# Stove_Light.net
KiCad netlist of a schematic drawn in Altium Designer
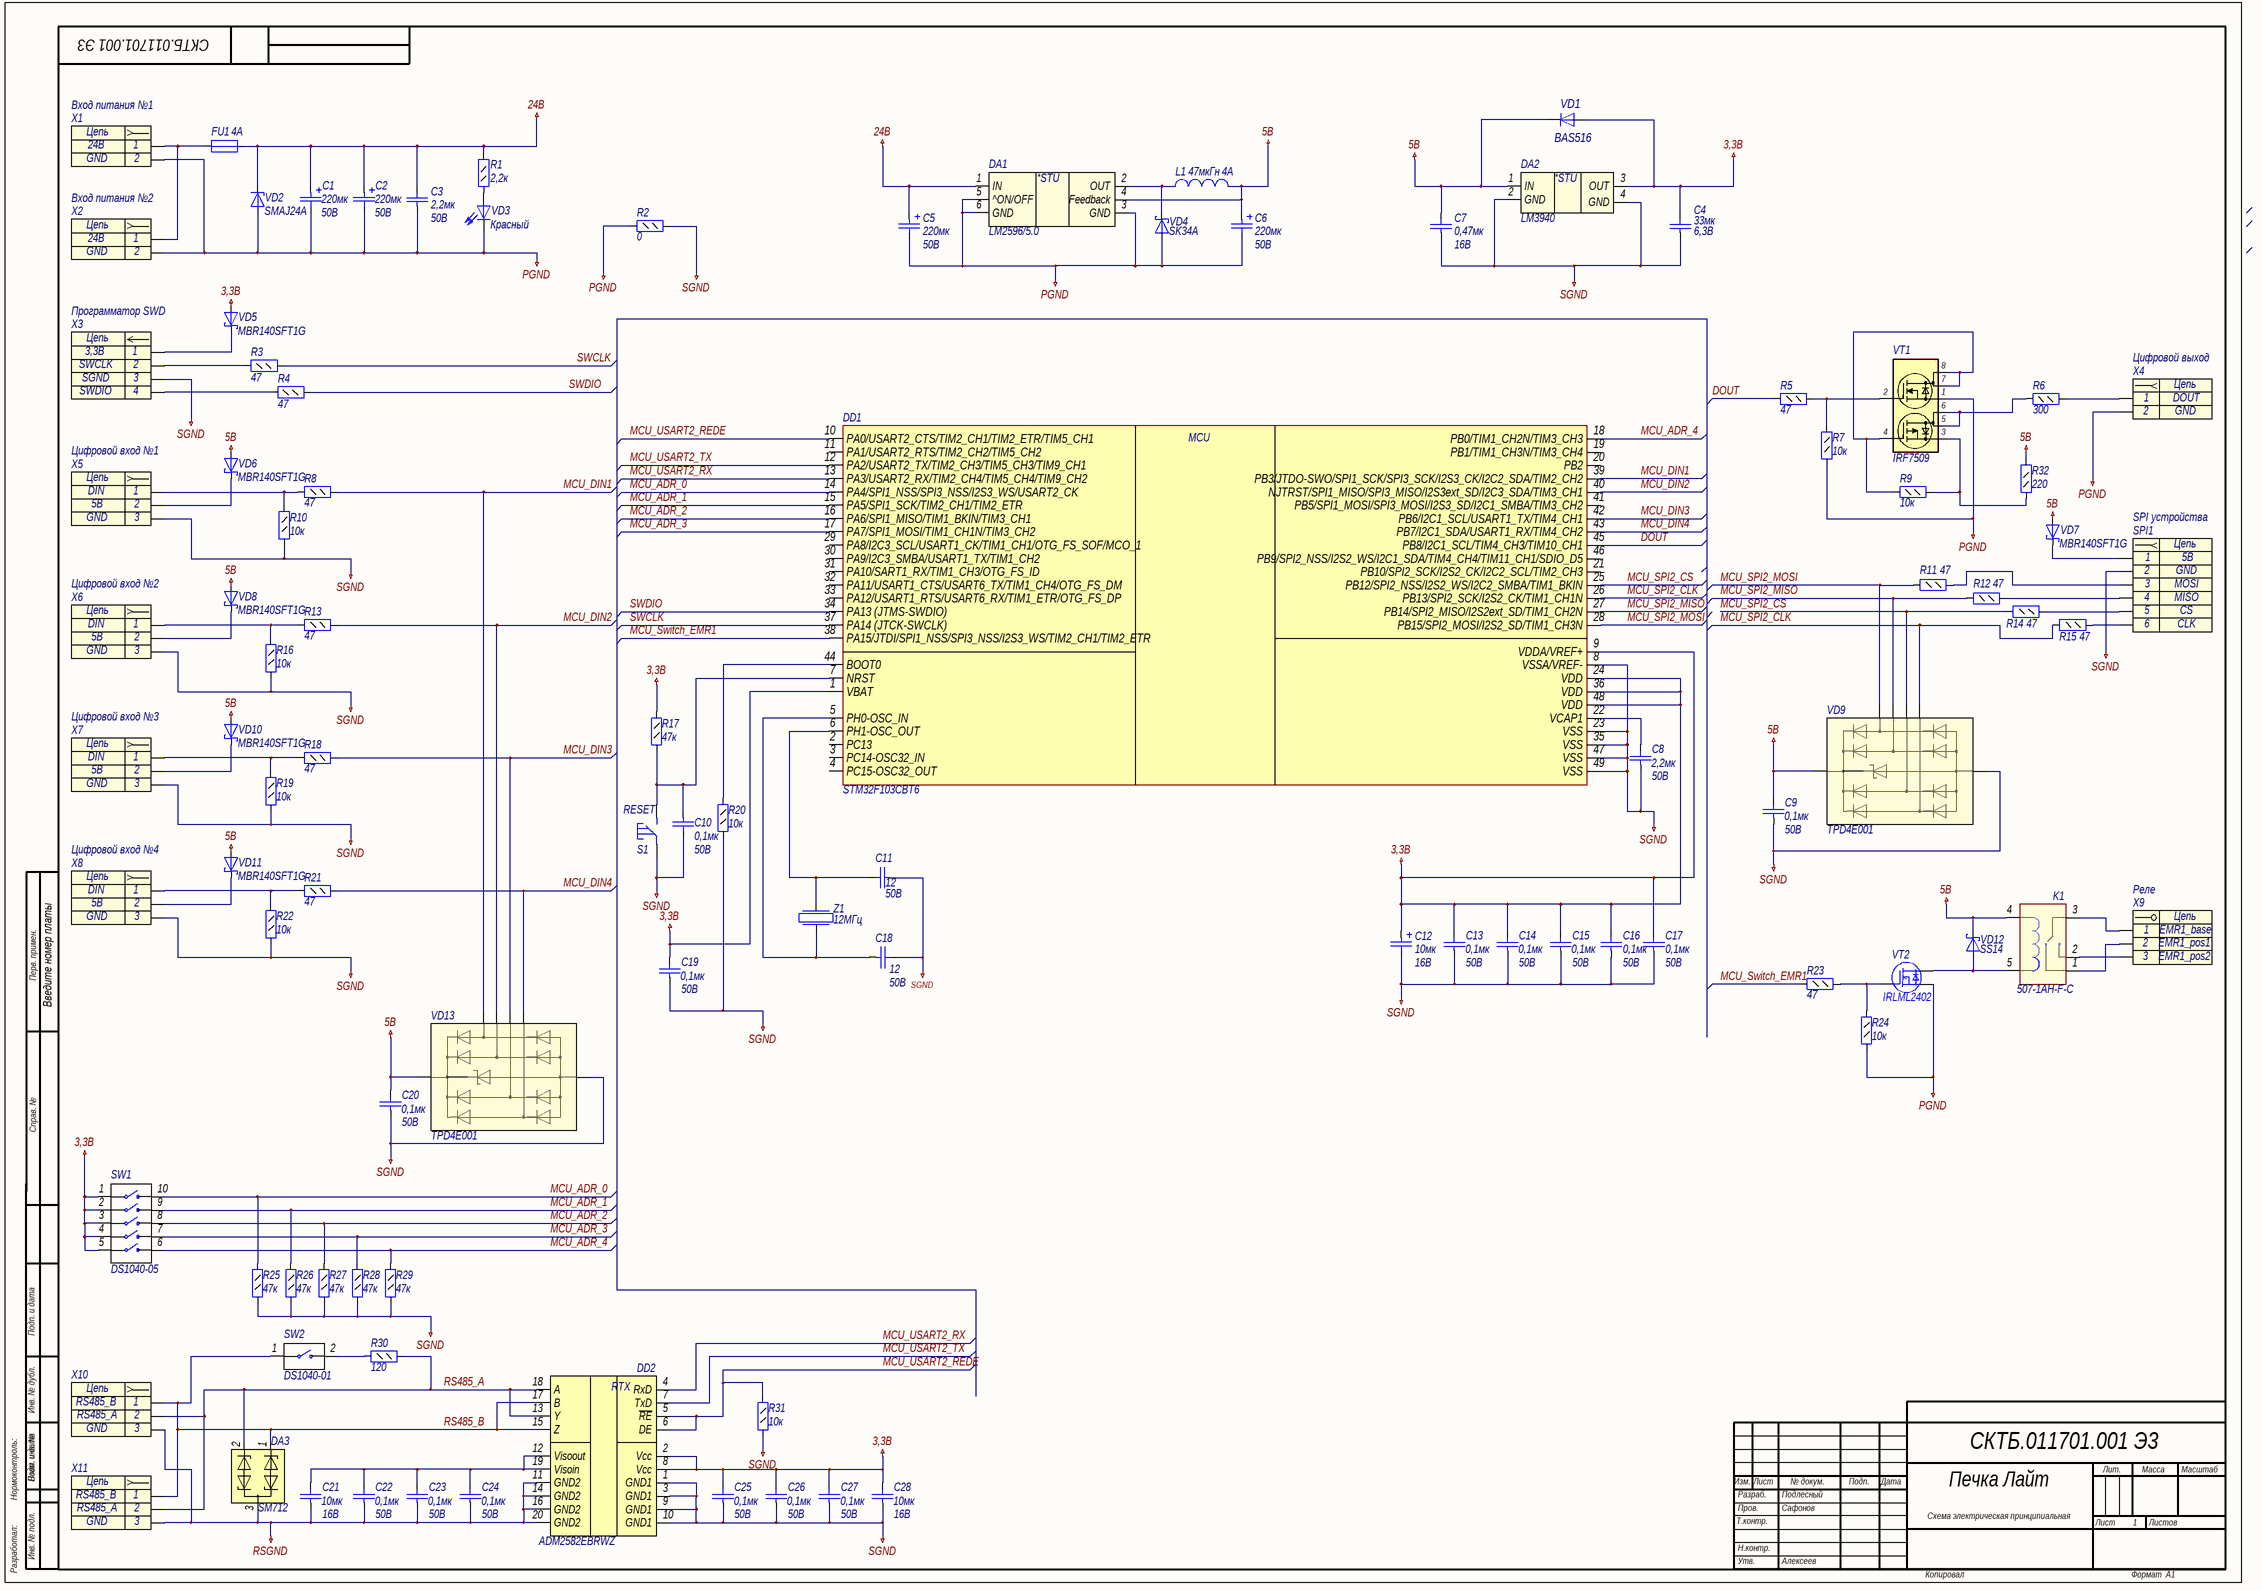
[diagram p0: Stove_Light.SchDoc]

(export (version "E")
  (design (tool "Eeschema 10.0.6"))
  (components
    (comp (ref "C1")
      (value "220мк")
      (footprint "Stove_Light:Cap_SMD_radial_polar(10x10.5)")
      (description "Конденсатор поляризованный")
      (fields (field (name "VOLTAGE") "50В"))
      (libsource (lib "Stove_Light") (part "Capacitor_pol"))
    )
    (comp (ref "C2")
      (value "220мк")
      (footprint "Stove_Light:Cap_SMD_radial_polar(10x10.5)")
      (description "Конденсатор поляризованный")
      (fields (field (name "VOLTAGE") "50В"))
      (libsource (lib "Stove_Light") (part "Capacitor_pol"))
    )
    (comp (ref "C3")
      (value "2,2мк")
      (footprint "Stove_Light:C1206")
      (description "Конденсатор")
      (fields (field (name "VOLTAGE") "50В"))
      (libsource (lib "Stove_Light") (part "Capacitor"))
    )
    (comp (ref "C4")
      (value "33мк")
      (footprint "Stove_Light:C1210")
      (description "Конденсатор")
      (fields (field (name "VOLTAGE") "6,3В") (field (name "Comment") "1мк"))
      (libsource (lib "Stove_Light") (part "Capacitor"))
    )
    (comp (ref "C5")
      (value "220мк")
      (footprint "Stove_Light:Cap_SMD_radial_polar(10x10.5)")
      (description "Конденсатор полярный")
      (fields (field (name "VOLTAGE") "50В"))
      (libsource (lib "Stove_Light") (part "Capacitor_pol"))
    )
    (comp (ref "C6")
      (value "220мк")
      (footprint "Stove_Light:Cap_SMD_radial_polar(10x10.5)")
      (description "Конденсатор полярный")
      (fields (field (name "VOLTAGE") "50В"))
      (libsource (lib "Stove_Light") (part "Capacitor_pol"))
    )
    (comp (ref "C7")
      (value "0,47мк")
      (footprint "Stove_Light:C0603")
      (description "Конденсатор")
      (fields (field (name "VOLTAGE") "16В"))
      (libsource (lib "Stove_Light") (part "Capacitor"))
    )
    (comp (ref "C8")
      (value "2,2мк")
      (footprint "Stove_Light:C1206")
      (description "Конденсатор")
      (fields (field (name "VOLTAGE") "50В"))
      (libsource (lib "Stove_Light") (part "Capacitor"))
    )
    (comp (ref "C9")
      (value "0,1мк")
      (footprint "Stove_Light:C0603")
      (description "Конденсатор")
      (fields (field (name "VOLTAGE") "50В"))
      (libsource (lib "Stove_Light") (part "Capacitor"))
    )
    (comp (ref "C10")
      (value "0,1мк")
      (footprint "Stove_Light:C0603")
      (description "Конденсатор")
      (fields (field (name "VOLTAGE") "50B"))
      (libsource (lib "Stove_Light") (part "Capacitor"))
    )
    (comp (ref "C11")
      (value "12")
      (footprint "Stove_Light:C0603")
      (description "Конденсатор")
      (fields (field (name "VOLTAGE") "50B"))
      (libsource (lib "Stove_Light") (part "Capacitor"))
    )
    (comp (ref "C12")
      (value "10мк")
      (footprint "Stove_Light:C1206")
      (description "Конденсатор танталовый")
      (fields (field (name "VOLTAGE") "16В"))
      (libsource (lib "Stove_Light") (part "Capacitor_pol"))
    )
    (comp (ref "C13")
      (value "0,1мк")
      (footprint "Stove_Light:C0603")
      (description "Конденсатор")
      (fields (field (name "VOLTAGE") "50В"))
      (libsource (lib "Stove_Light") (part "Capacitor"))
    )
    (comp (ref "C14")
      (value "0,1мк")
      (footprint "Stove_Light:C0603")
      (description "Конденсатор")
      (fields (field (name "VOLTAGE") "50В"))
      (libsource (lib "Stove_Light") (part "Capacitor"))
    )
    (comp (ref "C15")
      (value "0,1мк")
      (footprint "Stove_Light:C0603")
      (description "Конденсатор")
      (fields (field (name "VOLTAGE") "50В"))
      (libsource (lib "Stove_Light") (part "Capacitor"))
    )
    (comp (ref "C16")
      (value "0,1мк")
      (footprint "Stove_Light:C0603")
      (description "Конденсатор")
      (fields (field (name "VOLTAGE") "50В"))
      (libsource (lib "Stove_Light") (part "Capacitor"))
    )
    (comp (ref "C17")
      (value "0,1мк")
      (footprint "Stove_Light:C0603")
      (description "Конденсатор")
      (fields (field (name "VOLTAGE") "50В"))
      (libsource (lib "Stove_Light") (part "Capacitor"))
    )
    (comp (ref "C18")
      (value "12")
      (footprint "Stove_Light:C0603")
      (description "Конденсатор")
      (fields (field (name "VOLTAGE") "50В"))
      (libsource (lib "Stove_Light") (part "Capacitor"))
    )
    (comp (ref "C19")
      (value "0,1мк")
      (footprint "Stove_Light:C0603")
      (description "Конденсатор")
      (fields (field (name "VOLTAGE") "50В"))
      (libsource (lib "Stove_Light") (part "Capacitor"))
    )
    (comp (ref "C20")
      (value "0,1мк")
      (footprint "Stove_Light:C0603")
      (description "Конденсатор")
      (fields (field (name "VOLTAGE") "50В"))
      (libsource (lib "Stove_Light") (part "Capacitor"))
    )
    (comp (ref "C21")
      (value "10мк")
      (footprint "Stove_Light:C0603")
      (description "Конденсатор")
      (fields (field (name "VOLTAGE") "16В"))
      (libsource (lib "Stove_Light") (part "Capacitor"))
    )
    (comp (ref "C22")
      (value "0,1мк")
      (footprint "Stove_Light:C0603")
      (description "Конденсатор")
      (fields (field (name "VOLTAGE") "50В"))
      (libsource (lib "Stove_Light") (part "Capacitor"))
    )
    (comp (ref "C23")
      (value "0,1мк")
      (footprint "Stove_Light:C0603")
      (description "Конденсатор")
      (fields (field (name "VOLTAGE") "50В"))
      (libsource (lib "Stove_Light") (part "Capacitor"))
    )
    (comp (ref "C24")
      (value "0,1мк")
      (footprint "Stove_Light:C0603")
      (description "Конденсатор")
      (fields (field (name "VOLTAGE") "50В"))
      (libsource (lib "Stove_Light") (part "Capacitor"))
    )
    (comp (ref "C25")
      (value "0,1мк")
      (footprint "Stove_Light:C0603")
      (description "Конденсатор")
      (fields (field (name "VOLTAGE") "50В"))
      (libsource (lib "Stove_Light") (part "Capacitor"))
    )
    (comp (ref "C26")
      (value "0,1мк")
      (footprint "Stove_Light:C0603")
      (description "Конденсатор")
      (fields (field (name "VOLTAGE") "50В"))
      (libsource (lib "Stove_Light") (part "Capacitor"))
    )
    (comp (ref "C27")
      (value "0,1мк")
      (footprint "Stove_Light:C0603")
      (description "Конденсатор")
      (fields (field (name "VOLTAGE") "50В"))
      (libsource (lib "Stove_Light") (part "Capacitor"))
    )
    (comp (ref "C28")
      (value "10мк")
      (footprint "Stove_Light:C0603")
      (description "Конденсатор")
      (fields (field (name "VOLTAGE") "16В"))
      (libsource (lib "Stove_Light") (part "Capacitor"))
    )
    (comp (ref "DA1")
      (value "LM2596/5.0")
      (footprint "Stove_Light:TO-263")
      (description "3-A Step-Down Voltage Regulator")
      (libsource (lib "Stove_Light") (part "LM2596"))
    )
    (comp (ref "DA2")
      (value "LM3940")
      (footprint "Stove_Light:SOT223")
      (description "Low-Dropout Regulator for 5-V to 3.3-V Conversion")
      (libsource (lib "Stove_Light") (part "LM3940"))
    )
    (comp (ref "DA3")
      (value "SM712")
      (footprint "Stove_Light:SOT23-3")
      (description "SM712.TCT, Диод защитный для устройсв стандарта RS-485, 400Вт, 12В, [SOT-23]")
      (fields (field (name "POWER") "400Вт") (field (name "VOLTAGE") "12В"))
      (libsource (lib "Stove_Light") (part "SM712"))
    )
    (comp (ref "DD1")
      (value "STM32F103CBT6")
      (footprint "Stove_Light:LQFP48_N")
      (libsource (lib "Stove_Light") (part "STM32F104Cx"))
    )
    (comp (ref "DD2")
      (value "ADM2582EBRWZ")
      (footprint "Stove_Light:SO20W")
      (description "Приемопередатчик RS485 изолированный")
      (fields (field (name "NAME") "ADM2582EBRWZ"))
      (libsource (lib "Stove_Light") (part "ADM2587EBRWZ"))
    )
    (comp (ref "FU1")
      (value "4A")
      (footprint "Stove_Light:F5.1")
      (description "RXEF300 (RXE300), 3 А, Предохранитель самовосстанавливающийся, PolySwitch")
      (fields (field (name "Comment") "RXEF300"))
      (libsource (lib "Stove_Light") (part "Fuse"))
    )
    (comp (ref "K1")
      (value "507-1AH-F-C")
      (footprint "Stove_Light:EMR 845(H)-1C")
      (description "Электромагнитное реле")
      (libsource (lib "Stove_Light") (part "845(H)-1C"))
    )
    (comp (ref "L1")
      (value "47мкГн")
      (footprint "Stove_Light:SDR0604")
      (description "Катушка индуктивности")
      (fields (field (name "IMAX") "4А"))
      (libsource (lib "Stove_Light") (part "Inductor"))
    )
    (comp (ref "R1")
      (value "2,2к")
      (footprint "Stove_Light:R0603")
      (description "Резистор")
      (libsource (lib "") (part "Resistor_0,125Вт_3"))
    )
    (comp (ref "R2")
      (value "0")
      (footprint "Stove_Light:R0603")
      (description "Резистор")
      (libsource (lib "") (part "Resistor_0,125Вт_1"))
    )
    (comp (ref "R3")
      (value "47")
      (footprint "Stove_Light:R0603")
      (description "Резистор")
      (libsource (lib "") (part "Resistor_0,125Вт_2"))
    )
    (comp (ref "R4")
      (value "47")
      (footprint "Stove_Light:R0603")
      (description "Резистор")
      (libsource (lib "") (part "Resistor_0,125Вт_2"))
    )
    (comp (ref "R5")
      (value "47")
      (footprint "Stove_Light:R0603")
      (description "0.125Вт 0805 47 Ом, 1%, Чип резистор (SMD)")
      (libsource (lib "") (part "Resistor_0,125Вт_1"))
    )
    (comp (ref "R6")
      (value "300")
      (footprint "Stove_Light:R0603")
      (description "0.125Вт 0805 47 Ом, 1%, Чип резистор (SMD)")
      (libsource (lib "") (part "Resistor_0,125Вт_2"))
    )
    (comp (ref "R7")
      (value "10к")
      (footprint "Stove_Light:R0603")
      (description "0.125Вт 0805 47 Ом, 1%, Чип резистор (SMD)")
      (libsource (lib "Stove_Light") (part "Resistor_0,125Вт"))
    )
    (comp (ref "R8")
      (value "47")
      (footprint "Stove_Light:R0603")
      (description "0.125Вт 0805 47 Ом, 1%, Чип резистор (SMD)")
      (libsource (lib "") (part "Resistor_0,125Вт_1"))
    )
    (comp (ref "R9")
      (value "10к")
      (footprint "Stove_Light:R0603")
      (description "0.125Вт 0805 10 кОм, 1%, Чип резистор (SMD)")
      (libsource (lib "") (part "Resistor_0,125Вт_2"))
    )
    (comp (ref "R10")
      (value "10к")
      (footprint "Stove_Light:R0603")
      (description "0.125Вт 0805 10 кОм, 1%, Чип резистор (SMD)")
      (libsource (lib "Stove_Light") (part "Resistor_0,125Вт"))
    )
    (comp (ref "R11")
      (value "47")
      (footprint "Stove_Light:R0603")
      (description "0.125Вт 0805 47 Ом, 1%, Чип резистор (SMD)")
      (libsource (lib "") (part "Resistor_0,125Вт_1"))
    )
    (comp (ref "R12")
      (value "47")
      (footprint "Stove_Light:R0603")
      (description "0.125Вт 0805 47 Ом, 1%, Чип резистор (SMD)")
      (libsource (lib "") (part "Resistor_0,125Вт_1"))
    )
    (comp (ref "R13")
      (value "47")
      (footprint "Stove_Light:R0603")
      (description "0.125Вт 0805 47 Ом, 1%, Чип резистор (SMD)")
      (libsource (lib "") (part "Resistor_0,125Вт_1"))
    )
    (comp (ref "R14")
      (value "47")
      (footprint "Stove_Light:R0603")
      (description "0.125Вт 0805 47 Ом, 1%, Чип резистор (SMD)")
      (libsource (lib "") (part "Resistor_0,125Вт_1"))
    )
    (comp (ref "R15")
      (value "47")
      (footprint "Stove_Light:R0603")
      (description "0.125Вт 0805 47 Ом, 1%, Чип резистор (SMD)")
      (libsource (lib "") (part "Resistor_0,125Вт_1"))
    )
    (comp (ref "R16")
      (value "10к")
      (footprint "Stove_Light:R0603")
      (description "0.125Вт 0805 10 кОм, 1%, Чип резистор (SMD)")
      (libsource (lib "Stove_Light") (part "Resistor_0,125Вт"))
    )
    (comp (ref "R17")
      (value "47к")
      (footprint "Stove_Light:R0603")
      (description "0.125Вт 0805 10 кОм, 1%, Чип резистор (SMD)")
      (libsource (lib "Stove_Light") (part "Resistor_0,125Вт"))
    )
    (comp (ref "R18")
      (value "47")
      (footprint "Stove_Light:R0603")
      (description "0.125Вт 0805 47 Ом, 1%, Чип резистор (SMD)")
      (libsource (lib "") (part "Resistor_0,125Вт_1"))
    )
    (comp (ref "R19")
      (value "10к")
      (footprint "Stove_Light:R0603")
      (description "0.125Вт 0805 10 кОм, 1%, Чип резистор (SMD)")
      (libsource (lib "Stove_Light") (part "Resistor_0,125Вт"))
    )
    (comp (ref "R20")
      (value "10к")
      (footprint "Stove_Light:R0603")
      (description "0.125Вт 0805 10 кОм, 1%, Чип резистор (SMD)")
      (libsource (lib "Stove_Light") (part "Resistor_0,125Вт"))
    )
    (comp (ref "R21")
      (value "47")
      (footprint "Stove_Light:R0603")
      (description "0.125Вт 0805 47 Ом, 1%, Чип резистор (SMD)")
      (libsource (lib "") (part "Resistor_0,125Вт_1"))
    )
    (comp (ref "R22")
      (value "10к")
      (footprint "Stove_Light:R0603")
      (description "0.125Вт 0805 10 кОм, 1%, Чип резистор (SMD)")
      (libsource (lib "Stove_Light") (part "Resistor_0,125Вт"))
    )
    (comp (ref "R23")
      (value "47")
      (footprint "Stove_Light:R0603")
      (description "0.125Вт 0805 47 Ом, 1%, Чип резистор (SMD)")
      (libsource (lib "") (part "Resistor_0,125Вт_1"))
    )
    (comp (ref "R24")
      (value "10к")
      (footprint "Stove_Light:R0603")
      (description "0.125Вт 0805 10 кОм, 1%, Чип резистор (SMD)")
      (libsource (lib "Stove_Light") (part "Resistor_0,125Вт"))
    )
    (comp (ref "R25")
      (value "47к")
      (footprint "Stove_Light:R0603")
      (description "0.125Вт 0805 10 кОм, 1%, Чип резистор (SMD)")
      (libsource (lib "Stove_Light") (part "Resistor_0,125Вт"))
    )
    (comp (ref "R26")
      (value "47к")
      (footprint "Stove_Light:R0603")
      (description "0.125Вт 0805 10 кОм, 1%, Чип резистор (SMD)")
      (libsource (lib "Stove_Light") (part "Resistor_0,125Вт"))
    )
    (comp (ref "R27")
      (value "47к")
      (footprint "Stove_Light:R0603")
      (description "0.125Вт 0805 10 кОм, 1%, Чип резистор (SMD)")
      (libsource (lib "Stove_Light") (part "Resistor_0,125Вт"))
    )
    (comp (ref "R28")
      (value "47к")
      (footprint "Stove_Light:R0603")
      (description "0.125Вт 0805 10 кОм, 1%, Чип резистор (SMD)")
      (libsource (lib "Stove_Light") (part "Resistor_0,125Вт"))
    )
    (comp (ref "R29")
      (value "47к")
      (footprint "Stove_Light:R0603")
      (description "0.125Вт 0805 10 кОм, 1%, Чип резистор (SMD)")
      (libsource (lib "Stove_Light") (part "Resistor_0,125Вт"))
    )
    (comp (ref "R30")
      (value "120")
      (footprint "Stove_Light:R0603")
      (description "0.125Вт 0805 10 кОм, 1%, Чип резистор (SMD)")
      (libsource (lib "") (part "Resistor_0,125Вт_1"))
    )
    (comp (ref "R31")
      (value "10к")
      (footprint "Stove_Light:R0603")
      (description "0.125Вт 0805 10 кОм, 1%, Чип резистор (SMD)")
      (libsource (lib "Stove_Light") (part "Resistor_0,125Вт"))
    )
    (comp (ref "R32")
      (value "220")
      (footprint "Stove_Light:R0603")
      (description "0.125Вт 0805 47 Ом, 1%, Чип резистор (SMD)")
      (libsource (lib "") (part "Resistor_0,125Вт_3"))
    )
    (comp (ref "S1")
      (value "RESET")
      (footprint "Stove_Light:Button_SMD")
      (description "Кнопка")
      (fields (field (name "NAME") "RESET"))
      (libsource (lib "Stove_Light") (part "Button_SMD"))
    )
    (comp (ref "SPI1")
      (value "SPI устройства")
      (footprint "Stove_Light:CWF-6")
      (description "Разъем - 5 конт. розетка")
      (libsource (lib "Stove_Light") (part "Header_6_sct"))
    )
    (comp (ref "SW1")
      (value "DS1040-05")
      (footprint "Stove_Light:DIP5_R")
      (description "DIP переключатель")
      (libsource (lib "Stove_Light") (part "DS1040-05"))
    )
    (comp (ref "SW2")
      (value "DS1040-01")
      (footprint "Stove_Light:DIP1_R")
      (description "DIP переключатель")
      (libsource (lib "Stove_Light") (part "DS1040-01"))
    )
    (comp (ref "VD1")
      (value "BAS516")
      (footprint "Stove_Light:SOD523")
      (description "Диод")
      (libsource (lib "Stove_Light") (part "Diode"))
    )
    (comp (ref "VD2")
      (value "SMAJ24A")
      (footprint "Stove_Light:SMA")
      (description "Стабилитрон")
      (libsource (lib "Stove_Light") (part "DiodeZener"))
    )
    (comp (ref "VD3")
      (value "Красный")
      (footprint "Stove_Light:L_0805")
      (description "Светодиод_красный")
      (libsource (lib "Stove_Light") (part "LED_L"))
    )
    (comp (ref "VD4")
      (value "SK34A")
      (footprint "Stove_Light:SMA")
      (description "Диод Шоттки")
      (libsource (lib "Stove_Light") (part "DiodeSchottky"))
    )
    (comp (ref "VD5")
      (value "MBR140SFT1G")
      (footprint "Stove_Light:SMA")
      (description "Диод Шоттки")
      (libsource (lib "Stove_Light") (part "DiodeSchottky"))
    )
    (comp (ref "VD6")
      (value "MBR140SFT1G")
      (footprint "Stove_Light:SMA")
      (description "Диод Шоттки")
      (libsource (lib "Stove_Light") (part "DiodeSchottky"))
    )
    (comp (ref "VD7")
      (value "MBR140SFT1G")
      (footprint "Stove_Light:SMA")
      (description "Диод Шоттки")
      (libsource (lib "Stove_Light") (part "DiodeSchottky"))
    )
    (comp (ref "VD8")
      (value "MBR140SFT1G")
      (footprint "Stove_Light:SMA")
      (description "Диод Шоттки")
      (libsource (lib "Stove_Light") (part "DiodeSchottky"))
    )
    (comp (ref "VD9")
      (value "TPD4E001")
      (footprint "Stove_Light:SOT23-6")
      (description "Диодная сборка")
      (fields (field (name "MANUFACTURER") "Texas Instruments"))
      (libsource (lib "Stove_Light") (part "TPD4E001"))
    )
    (comp (ref "VD10")
      (value "MBR140SFT1G")
      (footprint "Stove_Light:SMA")
      (description "Диод Шоттки")
      (libsource (lib "Stove_Light") (part "DiodeSchottky"))
    )
    (comp (ref "VD11")
      (value "MBR140SFT1G")
      (footprint "Stove_Light:SMA")
      (description "Диод Шоттки")
      (libsource (lib "Stove_Light") (part "DiodeSchottky"))
    )
    (comp (ref "VD12")
      (value "SS14")
      (footprint "Stove_Light:SMA")
      (description "Диод Шоттки")
      (libsource (lib "Stove_Light") (part "DiodeSchottky"))
    )
    (comp (ref "VD13")
      (value "TPD4E001")
      (footprint "Stove_Light:SOT23-6")
      (description "Диодная сборка")
      (fields (field (name "MANUFACTURER") "Texas Instruments"))
      (libsource (lib "Stove_Light") (part "TPD4E001"))
    )
    (comp (ref "VT1")
      (value "IRF7509")
      (footprint "Stove_Light:Micro8")
      (description "Комплементарная сборка МОП")
      (fields (field (name "NAME") "IRF7509"))
      (libsource (lib "Stove_Light") (part "IRF7509"))
    )
    (comp (ref "VT2")
      (value "IRLML2402")
      (footprint "Stove_Light:SOT23-3_H")
      (description "MOSFET")
      (fields
        (field (name "MANUFACTURER") "International Rectifier")
        (field (name "MANUFACTURER PART NUMBER") "IRLML2402GTRPBF")
        (field (name "NAME") "IRLML2402")
      )
      (libsource (lib "Stove_Light") (part "IRLML2402"))
    )
    (comp (ref "X1")
      (value "Вход питания №1")
      (footprint "Stove_Light:CWF-2")
      (description "Разъем - 2 конт. розетка")
      (libsource (lib "Stove_Light") (part "Header_2_sct"))
    )
    (comp (ref "X2")
      (value "Вход питания №2")
      (footprint "Stove_Light:CWF-2")
      (description "Разъем - 2 конт. розетка")
      (libsource (lib "Stove_Light") (part "Header_2_sct"))
    )
    (comp (ref "X3")
      (value "Программатор SWD")
      (footprint "Stove_Light:PLS-4")
      (description "Разъем - 4 конт. вилка")
      (libsource (lib "Stove_Light") (part "Header_4_plg"))
    )
    (comp (ref "X4")
      (value "Цифровой выход")
      (footprint "Stove_Light:CWF-2")
      (description "Разъем - 2 конт. розетка")
      (libsource (lib "") (part "Header_2_sct_1"))
    )
    (comp (ref "X5")
      (value "Цифровой вход №1")
      (footprint "Stove_Light:CWF-3")
      (description "Разъем - 2 конт. розетка")
      (libsource (lib "Stove_Light") (part "Header_3_sct"))
    )
    (comp (ref "X6")
      (value "Цифровой вход №2")
      (footprint "Stove_Light:CWF-3")
      (description "Разъем - 2 конт. розетка")
      (libsource (lib "Stove_Light") (part "Header_3_sct"))
    )
    (comp (ref "X7")
      (value "Цифровой вход №3")
      (footprint "Stove_Light:CWF-3")
      (description "Разъем - 2 конт. розетка")
      (libsource (lib "Stove_Light") (part "Header_3_sct"))
    )
    (comp (ref "X8")
      (value "Цифровой вход №4")
      (footprint "Stove_Light:CWF-3")
      (description "Разъем - 2 конт. розетка")
      (libsource (lib "Stove_Light") (part "Header_3_sct"))
    )
    (comp (ref "X9")
      (value "Реле")
      (footprint "Stove_Light:DT-128V-3")
      (description "Разъем - 3 конт. клемма")
      (libsource (lib "Stove_Light") (part "Header_3_trm"))
    )
    (comp (ref "X10")
      (value "~")
      (footprint "Stove_Light:CWF-3")
      (description "Разъем - 2 конт. розетка")
      (libsource (lib "Stove_Light") (part "Header_3_sct"))
    )
    (comp (ref "X11")
      (value "~")
      (footprint "Stove_Light:CWF-3")
      (description "Разъем - 2 конт. розетка")
      (libsource (lib "Stove_Light") (part "Header_3_sct"))
    )
    (comp (ref "Z1")
      (value "12MГц")
      (footprint "Stove_Light:QSMD3.2x2.5_A")
      (description "Кварцевый резонатор")
      (libsource (lib "Stove_Light") (part "Crystal"))
    )
  )
  (nets
    (net (code "1") (name "/DOUT") (class "Default")
      (node (ref "DD1") (pin "45") (pinfunction "PB8/I2C1_SCL/TIM4_CH3/TIM10_CH1_45") (pintype "passive"))
      (node (ref "R5") (pin "2") (pinfunction "5_2") (pintype "passive"))
    )
    (net (code "2") (name "/MCU_ADR_0") (class "Default")
      (node (ref "DD1") (pin "14") (pinfunction "PA4/SPI1_NSS/SPI3_NSS/I2S3_WS/USART2_CK_14") (pintype "passive"))
      (node (ref "R25") (pin "1") (pinfunction "1_1") (pintype "passive"))
      (node (ref "SW1") (pin "10") (pintype "passive"))
    )
    (net (code "3") (name "/MCU_ADR_1") (class "Default")
      (node (ref "DD1") (pin "15") (pinfunction "PA5/SPI1_SCK/TIM2_CH1/TIM2_ETR_15") (pintype "passive"))
      (node (ref "R26") (pin "1") (pinfunction "1_1") (pintype "passive"))
      (node (ref "SW1") (pin "9") (pintype "passive"))
    )
    (net (code "4") (name "/MCU_ADR_2") (class "Default")
      (node (ref "DD1") (pin "16") (pinfunction "PA6/SPI1_MISO/TIM1_BKIN/TIM3_CH1_16") (pintype "passive"))
      (node (ref "R27") (pin "1") (pinfunction "1_1") (pintype "passive"))
      (node (ref "SW1") (pin "8") (pintype "passive"))
    )
    (net (code "5") (name "/MCU_ADR_3") (class "Default")
      (node (ref "DD1") (pin "17") (pinfunction "PA7/SPI1_MOSI/TIM1_CH1N/TIM3_CH2_17") (pintype "passive"))
      (node (ref "R28") (pin "1") (pinfunction "1_1") (pintype "passive"))
      (node (ref "SW1") (pin "7") (pintype "passive"))
    )
    (net (code "6") (name "/MCU_ADR_4") (class "Default")
      (node (ref "DD1") (pin "18") (pinfunction "PB0/TIM1_CH2N/TIM3_CH3_18") (pintype "passive"))
      (node (ref "R29") (pin "1") (pinfunction "1_1") (pintype "passive"))
      (node (ref "SW1") (pin "6") (pintype "passive"))
    )
    (net (code "7") (name "/MCU_DIN1") (class "Default")
      (node (ref "DD1") (pin "39") (pinfunction "PB3/JTDO-SWO/SPI1_SCK/SPI3_SCK/I2S3_CK/I2C2_SDA/TIM2_CH2_39") (pintype "passive"))
      (node (ref "R8") (pin "1") (pinfunction "1_1") (pintype "passive"))
      (node (ref "VD13") (pin "1") (pinfunction "IO1_1") (pintype "passive"))
    )
    (net (code "8") (name "/MCU_DIN2") (class "Default")
      (node (ref "DD1") (pin "40") (pinfunction "NJTRST/SPI1_MISO/SPI3_MISO/I2S3ext_SD/I2C3_SDA/TIM3_CH1_40") (pintype "passive"))
      (node (ref "R13") (pin "1") (pinfunction "1_1") (pintype "passive"))
      (node (ref "VD13") (pin "3") (pinfunction "IO2_3") (pintype "passive"))
    )
    (net (code "9") (name "/MCU_DIN3") (class "Default")
      (node (ref "DD1") (pin "42") (pinfunction "PB6/I2C1_SCL/USART1_TX/TIM4_CH1_42") (pintype "passive"))
      (node (ref "R18") (pin "1") (pinfunction "1_1") (pintype "passive"))
      (node (ref "VD13") (pin "4") (pinfunction "IO3_4") (pintype "passive"))
    )
    (net (code "10") (name "/MCU_DIN4") (class "Default")
      (node (ref "DD1") (pin "43") (pinfunction "PB7/I2C1_SDA/USART1_RX/TIM4_CH2_43") (pintype "passive"))
      (node (ref "R21") (pin "1") (pinfunction "1_1") (pintype "passive"))
      (node (ref "VD13") (pin "6") (pinfunction "IO4_6") (pintype "passive"))
    )
    (net (code "11") (name "/MCU_SPI2_CLK") (class "Default")
      (node (ref "DD1") (pin "26") (pinfunction "PB13/SPI2_SCK/I2S2_CK/TIM1_CH1N_26") (pintype "passive"))
      (node (ref "R15") (pin "2") (pinfunction "5_2") (pintype "passive"))
      (node (ref "VD9") (pin "6") (pinfunction "IO4_6") (pintype "passive"))
    )
    (net (code "12") (name "/MCU_SPI2_CS") (class "Default")
      (node (ref "DD1") (pin "25") (pinfunction "PB12/SPI2_NSS/I2S2_WS/I2C2_SMBA/TIM1_BKIN_25") (pintype "passive"))
      (node (ref "R14") (pin "2") (pinfunction "5_2") (pintype "passive"))
      (node (ref "VD9") (pin "4") (pinfunction "IO3_4") (pintype "passive"))
    )
    (net (code "13") (name "/MCU_SPI2_MISO") (class "Default")
      (node (ref "DD1") (pin "27") (pinfunction "PB14/SPI2_MISO/I2S2ext_SD/TIM1_CH2N_27") (pintype "passive"))
      (node (ref "R12") (pin "2") (pinfunction "5_2") (pintype "passive"))
      (node (ref "VD9") (pin "3") (pinfunction "IO2_3") (pintype "passive"))
    )
    (net (code "14") (name "/MCU_SPI2_MOSI") (class "Default")
      (node (ref "DD1") (pin "28") (pinfunction "PB15/SPI2_MOSI/I2S2_SD/TIM1_CH3N_28") (pintype "passive"))
      (node (ref "R11") (pin "2") (pinfunction "5_2") (pintype "passive"))
      (node (ref "VD9") (pin "1") (pinfunction "IO1_1") (pintype "passive"))
    )
    (net (code "15") (name "/MCU_Switch_EMR1") (class "Default")
      (node (ref "DD1") (pin "38") (pinfunction "PA15/JTDI/SPI1_NSS/SPI3_NSS/I2S3_WS/TIM2_CH1/TIM2_ETR_38") (pintype "passive"))
      (node (ref "R23") (pin "2") (pinfunction "5_2") (pintype "passive"))
    )
    (net (code "16") (name "/MCU_USART2_REDE") (class "Default")
      (node (ref "DD1") (pin "10") (pinfunction "PA0/USART2_CTS/TIM2_CH1/TIM2_ETR/TIM5_CH1_10") (pintype "passive"))
      (node (ref "DD2") (pin "5") (pinfunction "~{RE}_5") (pintype "passive"))
      (node (ref "DD2") (pin "6") (pinfunction "DE_6") (pintype "passive"))
      (node (ref "R31") (pin "1") (pinfunction "1_1") (pintype "passive"))
    )
    (net (code "17") (name "/MCU_USART2_RX") (class "Default")
      (node (ref "DD1") (pin "13") (pinfunction "PA3/USART2_RX/TIM2_CH4/TIM5_CH4/TIM9_CH2_13") (pintype "passive"))
      (node (ref "DD2") (pin "4") (pinfunction "RxD_4") (pintype "passive"))
    )
    (net (code "18") (name "/MCU_USART2_TX") (class "Default")
      (node (ref "DD1") (pin "12") (pinfunction "PA2/USART2_TX/TIM2_CH3/TIM5_CH3/TIM9_CH1_12") (pintype "passive"))
      (node (ref "DD2") (pin "7") (pinfunction "TxD_7") (pintype "passive"))
    )
    (net (code "19") (name "/RS485_A") (class "Default")
      (node (ref "DA3") (pin "2") (pinfunction "1_2") (pintype "passive"))
      (node (ref "DD2") (pin "13") (pinfunction "Y_13") (pintype "passive"))
      (node (ref "DD2") (pin "18") (pinfunction "A_18") (pintype "passive"))
      (node (ref "R30") (pin "1") (pinfunction "1_1") (pintype "passive"))
      (node (ref "X10") (pin "2") (pinfunction "2_2") (pintype "passive"))
      (node (ref "X11") (pin "2") (pinfunction "2_2") (pintype "passive"))
    )
    (net (code "20") (name "/RS485_B") (class "Default")
      (node (ref "DA3") (pin "1") (pintype "passive"))
      (node (ref "DD2") (pin "15") (pinfunction "Z_15") (pintype "passive"))
      (node (ref "DD2") (pin "17") (pinfunction "B_17") (pintype "passive"))
      (node (ref "SW2") (pin "1") (pintype "passive"))
      (node (ref "X10") (pin "1") (pinfunction "1_1") (pintype "passive"))
      (node (ref "X11") (pin "1") (pinfunction "1_1") (pintype "passive"))
    )
    (net (code "21") (name "/SWCLK") (class "Default")
      (node (ref "DD1") (pin "37") (pinfunction "PA14_(JTCK-SWCLK)_37") (pintype "passive"))
      (node (ref "R3") (pin "2") (pinfunction "5_2") (pintype "passive"))
    )
    (net (code "22") (name "/SWDIO") (class "Default")
      (node (ref "DD1") (pin "34") (pinfunction "PA13_(JTMS-SWDIO)_34") (pintype "passive"))
      (node (ref "R4") (pin "2") (pinfunction "5_2") (pintype "passive"))
    )
    (net (code "23") (name "3,3В") (class "Default")
      (node (ref "C12") (pin "1") (pinfunction "1_1") (pintype "passive"))
      (node (ref "C13") (pin "2") (pinfunction "2_2") (pintype "passive"))
      (node (ref "C14") (pin "2") (pinfunction "2_2") (pintype "passive"))
      (node (ref "C15") (pin "2") (pinfunction "2_2") (pintype "passive"))
      (node (ref "C16") (pin "2") (pinfunction "2_2") (pintype "passive"))
      (node (ref "C17") (pin "2") (pinfunction "2_2") (pintype "passive"))
      (node (ref "C19") (pin "2") (pinfunction "2_2") (pintype "passive"))
      (node (ref "C25") (pin "2") (pinfunction "2_2") (pintype "passive"))
      (node (ref "C26") (pin "2") (pinfunction "2_2") (pintype "passive"))
      (node (ref "C27") (pin "2") (pinfunction "2_2") (pintype "passive"))
      (node (ref "C28") (pin "2") (pinfunction "2_2") (pintype "passive"))
      (node (ref "C4") (pin "2") (pinfunction "2_2") (pintype "passive"))
      (node (ref "DA2") (pin "3") (pinfunction "OUT_3") (pintype "power_in"))
      (node (ref "DD1") (pin "1") (pinfunction "VBAT_1") (pintype "passive"))
      (node (ref "DD1") (pin "24") (pinfunction "VDD_24") (pintype "passive"))
      (node (ref "DD1") (pin "36") (pinfunction "VDD_36") (pintype "passive"))
      (node (ref "DD1") (pin "48") (pinfunction "VDD_48") (pintype "passive"))
      (node (ref "DD1") (pin "9") (pinfunction "VDDA/VREF+_9") (pintype "passive"))
      (node (ref "DD2") (pin "2") (pinfunction "Vcc_2") (pintype "passive"))
      (node (ref "DD2") (pin "8") (pinfunction "Vcc_8") (pintype "passive"))
      (node (ref "R17") (pin "1") (pinfunction "1_1") (pintype "passive"))
      (node (ref "SW1") (pin "1") (pintype "passive"))
      (node (ref "SW1") (pin "2") (pintype "passive"))
      (node (ref "SW1") (pin "3") (pintype "passive"))
      (node (ref "SW1") (pin "4") (pintype "passive"))
      (node (ref "SW1") (pin "5") (pintype "passive"))
      (node (ref "VD1") (pin "2") (pinfunction "A_2") (pintype "passive"))
      (node (ref "VD5") (pin "2") (pinfunction "A_2") (pintype "passive"))
    )
    (net (code "24") (name "5В") (class "Default")
      (node (ref "C20") (pin "2") (pinfunction "2_2") (pintype "passive"))
      (node (ref "C6") (pin "1") (pinfunction "1_1") (pintype "passive"))
      (node (ref "C7") (pin "2") (pinfunction "2_2") (pintype "passive"))
      (node (ref "C9") (pin "2") (pinfunction "2_2") (pintype "passive"))
      (node (ref "DA1") (pin "4") (pinfunction "Feedback_4") (pintype "power_in"))
      (node (ref "DA2") (pin "1") (pinfunction "IN_1") (pintype "power_in"))
      (node (ref "K1") (pin "4") (pinfunction "sw1_4") (pintype "passive"))
      (node (ref "L1") (pin "2") (pinfunction "2_2") (pintype "passive"))
      (node (ref "R32") (pin "2") (pinfunction "5_2") (pintype "passive"))
      (node (ref "VD1") (pin "1") (pinfunction "K_1") (pintype "passive"))
      (node (ref "VD10") (pin "2") (pinfunction "A_2") (pintype "passive"))
      (node (ref "VD11") (pin "2") (pinfunction "A_2") (pintype "passive"))
      (node (ref "VD12") (pin "1") (pinfunction "K_1") (pintype "passive"))
      (node (ref "VD13") (pin "5") (pinfunction "VCC_5") (pintype "passive"))
      (node (ref "VD6") (pin "2") (pinfunction "A_2") (pintype "passive"))
      (node (ref "VD7") (pin "2") (pinfunction "A_2") (pintype "passive"))
      (node (ref "VD8") (pin "2") (pinfunction "A_2") (pintype "passive"))
      (node (ref "VD9") (pin "5") (pinfunction "VCC_5") (pintype "passive"))
    )
    (net (code "25") (name "24В") (class "Default")
      (node (ref "C1") (pin "1") (pinfunction "1_1") (pintype "passive"))
      (node (ref "C2") (pin "1") (pinfunction "1_1") (pintype "passive"))
      (node (ref "C3") (pin "2") (pinfunction "2_2") (pintype "passive"))
      (node (ref "C5") (pin "1") (pinfunction "1_1") (pintype "passive"))
      (node (ref "DA1") (pin "1") (pinfunction "IN_1") (pintype "power_in"))
      (node (ref "FU1") (pin "2") (pinfunction "2_2") (pintype "passive"))
      (node (ref "R1") (pin "2") (pinfunction "5_2") (pintype "passive"))
      (node (ref "VD2") (pin "1") (pinfunction "K_1") (pintype "passive"))
    )
    (net (code "26") (name "Net-(DA1-OUT)") (class "Default")
      (node (ref "DA1") (pin "2") (pinfunction "OUT_2") (pintype "power_in"))
      (node (ref "L1") (pin "1") (pinfunction "1_1") (pintype "passive"))
      (node (ref "VD4") (pin "1") (pinfunction "K_1") (pintype "passive"))
    )
    (net (code "27") (name "Net-(DD1-BOOT0)") (class "Default")
      (node (ref "DD1") (pin "44") (pinfunction "BOOT0_44") (pintype "passive"))
      (node (ref "R20") (pin "1") (pinfunction "1_1") (pintype "passive"))
    )
    (net (code "28") (name "Net-(DD1-NRST)") (class "Default")
      (node (ref "C10") (pin "1") (pinfunction "1_1") (pintype "passive"))
      (node (ref "DD1") (pin "7") (pinfunction "NRST_7") (pintype "passive"))
      (node (ref "R17") (pin "2") (pinfunction "5_2") (pintype "passive"))
      (node (ref "S1") (pin "3") (pinfunction "3_3") (pintype "passive"))
    )
    (net (code "29") (name "Net-(DD1-PH0-OSC_IN)") (class "Default")
      (node (ref "C18") (pin "1") (pinfunction "1_1") (pintype "passive"))
      (node (ref "DD1") (pin "5") (pinfunction "PH0-OSC_IN_5") (pintype "passive"))
      (node (ref "Z1") (pin "2") (pinfunction "2_2") (pintype "passive"))
    )
    (net (code "30") (name "Net-(DD1-PH1-OSC_OUT)") (class "Default")
      (node (ref "C11") (pin "2") (pinfunction "2_2") (pintype "passive"))
      (node (ref "DD1") (pin "6") (pinfunction "PH1-OSC_OUT_6") (pintype "passive"))
      (node (ref "Z1") (pin "1") (pinfunction "1_1") (pintype "passive"))
    )
    (net (code "31") (name "Net-(DD1-VCAP1)") (class "Default")
      (node (ref "C8") (pin "2") (pinfunction "2_2") (pintype "passive"))
      (node (ref "DD1") (pin "22") (pinfunction "VCAP1_22") (pintype "passive"))
    )
    (net (code "32") (name "Net-(DD2-Visoin)") (class "Default")
      (node (ref "C21") (pin "2") (pinfunction "2_2") (pintype "passive"))
      (node (ref "C22") (pin "2") (pinfunction "2_2") (pintype "passive"))
      (node (ref "C23") (pin "2") (pinfunction "2_2") (pintype "passive"))
      (node (ref "C24") (pin "2") (pinfunction "2_2") (pintype "passive"))
      (node (ref "DD2") (pin "12") (pinfunction "Visoout_12") (pintype "passive"))
      (node (ref "DD2") (pin "19") (pinfunction "Visoin_19") (pintype "passive"))
    )
    (net (code "33") (name "Net-(FU1-Pad1)") (class "Default")
      (node (ref "FU1") (pin "1") (pinfunction "1_1") (pintype "passive"))
      (node (ref "X1") (pin "1") (pinfunction "1_1") (pintype "passive"))
      (node (ref "X2") (pin "1") (pinfunction "1_1") (pintype "passive"))
    )
    (net (code "34") (name "Net-(K1-base)") (class "Default")
      (node (ref "K1") (pin "3") (pinfunction "base_3") (pintype "passive"))
      (node (ref "X9") (pin "1") (pinfunction "1_1") (pintype "passive"))
    )
    (net (code "35") (name "Net-(K1-pos1)") (class "Default")
      (node (ref "K1") (pin "1") (pinfunction "pos1_1") (pintype "passive"))
      (node (ref "X9") (pin "2") (pinfunction "2_2") (pintype "passive"))
    )
    (net (code "36") (name "Net-(K1-pos2)") (class "Default")
      (node (ref "K1") (pin "2") (pinfunction "pos2_2") (pintype "passive"))
      (node (ref "X9") (pin "3") (pinfunction "3_3") (pintype "passive"))
    )
    (net (code "37") (name "Net-(K1-sw2)") (class "Default")
      (node (ref "K1") (pin "5") (pinfunction "sw2_5") (pintype "passive"))
      (node (ref "VD12") (pin "2") (pinfunction "A_2") (pintype "passive"))
      (node (ref "VT2") (pin "3") (pinfunction "D_3") (pintype "passive"))
    )
    (net (code "38") (name "Net-(R3-Pad1)") (class "Default")
      (node (ref "R3") (pin "1") (pinfunction "1_1") (pintype "passive"))
      (node (ref "X3") (pin "2") (pinfunction "2_2") (pintype "passive"))
    )
    (net (code "39") (name "Net-(R4-Pad1)") (class "Default")
      (node (ref "R4") (pin "1") (pinfunction "1_1") (pintype "passive"))
      (node (ref "X3") (pin "4") (pinfunction "4_4") (pintype "passive"))
    )
    (net (code "40") (name "Net-(R6-5)") (class "Default")
      (node (ref "R6") (pin "2") (pinfunction "5_2") (pintype "passive"))
      (node (ref "X4") (pin "1") (pinfunction "1_1") (pintype "passive"))
    )
    (net (code "41") (name "Net-(R6-Pad1)") (class "Default")
      (node (ref "R6") (pin "1") (pinfunction "1_1") (pintype "passive"))
      (node (ref "VT1") (pin "5") (pinfunction "D2_5") (pintype "passive"))
      (node (ref "VT1") (pin "6") (pinfunction "D2_6") (pintype "passive"))
    )
    (net (code "42") (name "Net-(R8-5)") (class "Default")
      (node (ref "R10") (pin "1") (pinfunction "1_1") (pintype "passive"))
      (node (ref "R8") (pin "2") (pinfunction "5_2") (pintype "passive"))
      (node (ref "X5") (pin "1") (pinfunction "1_1") (pintype "passive"))
    )
    (net (code "43") (name "Net-(R9-5)") (class "Default")
      (node (ref "R32") (pin "1") (pinfunction "1_1") (pintype "passive"))
      (node (ref "R9") (pin "2") (pinfunction "5_2") (pintype "passive"))
      (node (ref "VT1") (pin "3") (pinfunction "S2_3") (pintype "passive"))
    )
    (net (code "44") (name "Net-(R11-Pad1)") (class "Default")
      (node (ref "R11") (pin "1") (pinfunction "1_1") (pintype "passive"))
      (node (ref "SPI1") (pin "3") (pinfunction "3_3") (pintype "passive"))
    )
    (net (code "45") (name "Net-(R12-Pad1)") (class "Default")
      (node (ref "R12") (pin "1") (pinfunction "1_1") (pintype "passive"))
      (node (ref "SPI1") (pin "4") (pinfunction "4_4") (pintype "passive"))
    )
    (net (code "46") (name "Net-(R13-5)") (class "Default")
      (node (ref "R13") (pin "2") (pinfunction "5_2") (pintype "passive"))
      (node (ref "R16") (pin "1") (pinfunction "1_1") (pintype "passive"))
      (node (ref "X6") (pin "1") (pinfunction "1_1") (pintype "passive"))
    )
    (net (code "47") (name "Net-(R14-Pad1)") (class "Default")
      (node (ref "R14") (pin "1") (pinfunction "1_1") (pintype "passive"))
      (node (ref "SPI1") (pin "5") (pinfunction "5_5") (pintype "passive"))
    )
    (net (code "48") (name "Net-(R15-Pad1)") (class "Default")
      (node (ref "R15") (pin "1") (pinfunction "1_1") (pintype "passive"))
      (node (ref "SPI1") (pin "6") (pinfunction "6_6") (pintype "passive"))
    )
    (net (code "49") (name "Net-(R18-5)") (class "Default")
      (node (ref "R18") (pin "2") (pinfunction "5_2") (pintype "passive"))
      (node (ref "R19") (pin "1") (pinfunction "1_1") (pintype "passive"))
      (node (ref "X7") (pin "1") (pinfunction "1_1") (pintype "passive"))
    )
    (net (code "50") (name "Net-(R21-5)") (class "Default")
      (node (ref "R21") (pin "2") (pinfunction "5_2") (pintype "passive"))
      (node (ref "R22") (pin "1") (pinfunction "1_1") (pintype "passive"))
      (node (ref "X8") (pin "1") (pinfunction "1_1") (pintype "passive"))
    )
    (net (code "51") (name "Net-(R30-5)") (class "Default")
      (node (ref "R30") (pin "2") (pinfunction "5_2") (pintype "passive"))
      (node (ref "SW2") (pin "2") (pintype "passive"))
    )
    (net (code "52") (name "Net-(VD3-A)") (class "Default")
      (node (ref "R1") (pin "1") (pinfunction "1_1") (pintype "passive"))
      (node (ref "VD3") (pin "2") (pinfunction "A_2") (pintype "passive"))
    )
    (net (code "53") (name "Net-(VD5-K)") (class "Default")
      (node (ref "VD5") (pin "1") (pinfunction "K_1") (pintype "passive"))
      (node (ref "X3") (pin "1") (pinfunction "1_1") (pintype "passive"))
    )
    (net (code "54") (name "Net-(VD6-K)") (class "Default")
      (node (ref "VD6") (pin "1") (pinfunction "K_1") (pintype "passive"))
      (node (ref "X5") (pin "2") (pinfunction "2_2") (pintype "passive"))
    )
    (net (code "55") (name "Net-(VD7-K)") (class "Default")
      (node (ref "SPI1") (pin "1") (pinfunction "1_1") (pintype "passive"))
      (node (ref "VD7") (pin "1") (pinfunction "K_1") (pintype "passive"))
    )
    (net (code "56") (name "Net-(VD8-K)") (class "Default")
      (node (ref "VD8") (pin "1") (pinfunction "K_1") (pintype "passive"))
      (node (ref "X6") (pin "2") (pinfunction "2_2") (pintype "passive"))
    )
    (net (code "57") (name "Net-(VD10-K)") (class "Default")
      (node (ref "VD10") (pin "1") (pinfunction "K_1") (pintype "passive"))
      (node (ref "X7") (pin "2") (pinfunction "2_2") (pintype "passive"))
    )
    (net (code "58") (name "Net-(VD11-K)") (class "Default")
      (node (ref "VD11") (pin "1") (pinfunction "K_1") (pintype "passive"))
      (node (ref "X8") (pin "2") (pinfunction "2_2") (pintype "passive"))
    )
    (net (code "59") (name "Net-(VT1-G1)") (class "Default")
      (node (ref "R5") (pin "1") (pinfunction "1_1") (pintype "passive"))
      (node (ref "R7") (pin "1") (pinfunction "1_1") (pintype "passive"))
      (node (ref "VT1") (pin "2") (pinfunction "G1_2") (pintype "passive"))
    )
    (net (code "60") (name "Net-(VT1-G2)") (class "Default")
      (node (ref "R9") (pin "1") (pinfunction "1_1") (pintype "passive"))
      (node (ref "VT1") (pin "4") (pinfunction "G2_4") (pintype "passive"))
      (node (ref "VT1") (pin "7") (pinfunction "D1_7") (pintype "passive"))
      (node (ref "VT1") (pin "8") (pinfunction "D1_8") (pintype "passive"))
    )
    (net (code "61") (name "Net-(VT2-G)") (class "Default")
      (node (ref "R23") (pin "1") (pinfunction "1_1") (pintype "passive"))
      (node (ref "R24") (pin "1") (pinfunction "1_1") (pintype "passive"))
      (node (ref "VT2") (pin "1") (pinfunction "G_1") (pintype "passive"))
    )
    (net (code "62") (name "PGND") (class "Default")
      (node (ref "C1") (pin "2") (pinfunction "2_2") (pintype "passive"))
      (node (ref "C2") (pin "2") (pinfunction "2_2") (pintype "passive"))
      (node (ref "C3") (pin "1") (pinfunction "1_1") (pintype "passive"))
      (node (ref "C5") (pin "2") (pinfunction "2_2") (pintype "passive"))
      (node (ref "C6") (pin "2") (pinfunction "2_2") (pintype "passive"))
      (node (ref "DA1") (pin "3") (pinfunction "GND_3") (pintype "power_in"))
      (node (ref "DA1") (pin "5") (pinfunction "^ON/OFF_5") (pintype "power_in"))
      (node (ref "DA1") (pin "6") (pinfunction "GND_6") (pintype "power_in"))
      (node (ref "R2") (pin "2") (pinfunction "5_2") (pintype "passive"))
      (node (ref "R24") (pin "2") (pinfunction "5_2") (pintype "passive"))
      (node (ref "R7") (pin "2") (pinfunction "5_2") (pintype "passive"))
      (node (ref "VD2") (pin "2") (pinfunction "A_2") (pintype "passive"))
      (node (ref "VD3") (pin "1") (pinfunction "K_1") (pintype "passive"))
      (node (ref "VD4") (pin "2") (pinfunction "A_2") (pintype "passive"))
      (node (ref "VT1") (pin "1") (pinfunction "S1_1") (pintype "passive"))
      (node (ref "VT2") (pin "2") (pinfunction "S_2") (pintype "passive"))
      (node (ref "X1") (pin "2") (pinfunction "2_2") (pintype "passive"))
      (node (ref "X2") (pin "2") (pinfunction "2_2") (pintype "passive"))
      (node (ref "X4") (pin "2") (pinfunction "2_2") (pintype "passive"))
    )
    (net (code "63") (name "RSGND") (class "Default")
      (node (ref "C21") (pin "1") (pinfunction "1_1") (pintype "passive"))
      (node (ref "C22") (pin "1") (pinfunction "1_1") (pintype "passive"))
      (node (ref "C23") (pin "1") (pinfunction "1_1") (pintype "passive"))
      (node (ref "C24") (pin "1") (pinfunction "1_1") (pintype "passive"))
      (node (ref "DA3") (pin "3") (pintype "passive"))
      (node (ref "DD2") (pin "11") (pinfunction "GND2_11") (pintype "passive"))
      (node (ref "DD2") (pin "14") (pinfunction "GND2_14") (pintype "passive"))
      (node (ref "DD2") (pin "16") (pinfunction "GND2_16") (pintype "passive"))
      (node (ref "DD2") (pin "20") (pinfunction "GND2_20") (pintype "passive"))
      (node (ref "X10") (pin "3") (pinfunction "3_3") (pintype "passive"))
      (node (ref "X11") (pin "3") (pinfunction "3_3") (pintype "passive"))
    )
    (net (code "64") (name "SGND") (class "Default")
      (node (ref "C10") (pin "2") (pinfunction "2_2") (pintype "passive"))
      (node (ref "C11") (pin "1") (pinfunction "1_1") (pintype "passive"))
      (node (ref "C12") (pin "2") (pinfunction "2_2") (pintype "passive"))
      (node (ref "C13") (pin "1") (pinfunction "1_1") (pintype "passive"))
      (node (ref "C14") (pin "1") (pinfunction "1_1") (pintype "passive"))
      (node (ref "C15") (pin "1") (pinfunction "1_1") (pintype "passive"))
      (node (ref "C16") (pin "1") (pinfunction "1_1") (pintype "passive"))
      (node (ref "C17") (pin "1") (pinfunction "1_1") (pintype "passive"))
      (node (ref "C18") (pin "2") (pinfunction "2_2") (pintype "passive"))
      (node (ref "C19") (pin "1") (pinfunction "1_1") (pintype "passive"))
      (node (ref "C20") (pin "1") (pinfunction "1_1") (pintype "passive"))
      (node (ref "C25") (pin "1") (pinfunction "1_1") (pintype "passive"))
      (node (ref "C26") (pin "1") (pinfunction "1_1") (pintype "passive"))
      (node (ref "C27") (pin "1") (pinfunction "1_1") (pintype "passive"))
      (node (ref "C28") (pin "1") (pinfunction "1_1") (pintype "passive"))
      (node (ref "C4") (pin "1") (pinfunction "1_1") (pintype "passive"))
      (node (ref "C7") (pin "1") (pinfunction "1_1") (pintype "passive"))
      (node (ref "C8") (pin "1") (pinfunction "1_1") (pintype "passive"))
      (node (ref "C9") (pin "1") (pinfunction "1_1") (pintype "passive"))
      (node (ref "DA2") (pin "2") (pinfunction "GND_2") (pintype "power_in"))
      (node (ref "DA2") (pin "4") (pinfunction "GND_4") (pintype "power_in"))
      (node (ref "DD1") (pin "23") (pinfunction "VSS_23") (pintype "passive"))
      (node (ref "DD1") (pin "35") (pinfunction "VSS_35") (pintype "passive"))
      (node (ref "DD1") (pin "47") (pinfunction "VSS_47") (pintype "passive"))
      (node (ref "DD1") (pin "49") (pinfunction "VSS_49") (pintype "passive"))
      (node (ref "DD1") (pin "8") (pinfunction "VSSA/VREF-_8") (pintype "passive"))
      (node (ref "DD2") (pin "1") (pinfunction "GND1_1") (pintype "passive"))
      (node (ref "DD2") (pin "10") (pinfunction "GND1_10") (pintype "passive"))
      (node (ref "DD2") (pin "3") (pinfunction "GND1_3") (pintype "passive"))
      (node (ref "DD2") (pin "9") (pinfunction "GND1_9") (pintype "passive"))
      (node (ref "R10") (pin "2") (pinfunction "5_2") (pintype "passive"))
      (node (ref "R16") (pin "2") (pinfunction "5_2") (pintype "passive"))
      (node (ref "R19") (pin "2") (pinfunction "5_2") (pintype "passive"))
      (node (ref "R2") (pin "1") (pinfunction "1_1") (pintype "passive"))
      (node (ref "R20") (pin "2") (pinfunction "5_2") (pintype "passive"))
      (node (ref "R22") (pin "2") (pinfunction "5_2") (pintype "passive"))
      (node (ref "R25") (pin "2") (pinfunction "5_2") (pintype "passive"))
      (node (ref "R26") (pin "2") (pinfunction "5_2") (pintype "passive"))
      (node (ref "R27") (pin "2") (pinfunction "5_2") (pintype "passive"))
      (node (ref "R28") (pin "2") (pinfunction "5_2") (pintype "passive"))
      (node (ref "R29") (pin "2") (pinfunction "5_2") (pintype "passive"))
      (node (ref "R31") (pin "2") (pinfunction "5_2") (pintype "passive"))
      (node (ref "S1") (pin "1") (pinfunction "1_1") (pintype "passive"))
      (node (ref "SPI1") (pin "2") (pinfunction "2_2") (pintype "passive"))
      (node (ref "VD13") (pin "2") (pinfunction "GND_2") (pintype "passive"))
      (node (ref "VD9") (pin "2") (pinfunction "GND_2") (pintype "passive"))
      (node (ref "X3") (pin "3") (pinfunction "3_3") (pintype "passive"))
      (node (ref "X5") (pin "3") (pinfunction "3_3") (pintype "passive"))
      (node (ref "X6") (pin "3") (pinfunction "3_3") (pintype "passive"))
      (node (ref "X7") (pin "3") (pinfunction "3_3") (pintype "passive"))
      (node (ref "X8") (pin "3") (pinfunction "3_3") (pintype "passive"))
    )
    (net (code "65") (name "unconnected-(DD1-PA1{slash}USART2_RTS{slash}TIM2_CH2{slash}TIM5_CH2-Pad11)") (class "Default")
      (node (ref "DD1") (pin "11") (pinfunction "PA1/USART2_RTS/TIM2_CH2/TIM5_CH2_11") (pintype "passive"))
    )
    (net (code "66") (name "unconnected-(DD1-PA8{slash}I2C3_SCL{slash}USART1_CK{slash}TIM1_CH1{slash}OTG_FS_SOF{slash}MCO_1-Pad29)") (class "Default")
      (node (ref "DD1") (pin "29") (pinfunction "PA8/I2C3_SCL/USART1_CK/TIM1_CH1/OTG_FS_SOF/MCO_1_29") (pintype "passive"))
    )
    (net (code "67") (name "unconnected-(DD1-PA9{slash}I2C3_SMBA{slash}USART1_TX{slash}TIM1_CH2-Pad30)") (class "Default")
      (node (ref "DD1") (pin "30") (pinfunction "PA9/I2C3_SMBA/USART1_TX/TIM1_CH2_30") (pintype "passive"))
    )
    (net (code "68") (name "unconnected-(DD1-PA10{slash}SART1_RX{slash}TIM1_CH3{slash}OTG_FS_ID-Pad31)") (class "Default")
      (node (ref "DD1") (pin "31") (pinfunction "PA10/SART1_RX/TIM1_CH3/OTG_FS_ID_31") (pintype "passive"))
    )
    (net (code "69") (name "unconnected-(DD1-PA11{slash}USART1_CTS{slash}USART6_TX{slash}TIM1_CH4{slash}OTG_FS_DM-Pad32)") (class "Default")
      (node (ref "DD1") (pin "32") (pinfunction "PA11/USART1_CTS/USART6_TX/TIM1_CH4/OTG_FS_DM_32") (pintype "passive"))
    )
    (net (code "70") (name "unconnected-(DD1-PA12{slash}USART1_RTS{slash}USART6_RX{slash}TIM1_ETR{slash}OTG_FS_DP-Pad33)") (class "Default")
      (node (ref "DD1") (pin "33") (pinfunction "PA12/USART1_RTS/USART6_RX/TIM1_ETR/OTG_FS_DP_33") (pintype "passive"))
    )
    (net (code "71") (name "unconnected-(DD1-PB1{slash}TIM1_CH3N{slash}TIM3_CH4-Pad19)") (class "Default")
      (node (ref "DD1") (pin "19") (pinfunction "PB1/TIM1_CH3N/TIM3_CH4_19") (pintype "passive"))
    )
    (net (code "72") (name "unconnected-(DD1-PB2-Pad20)") (class "Default")
      (node (ref "DD1") (pin "20") (pinfunction "PB2_20") (pintype "passive"))
    )
    (net (code "73") (name "unconnected-(DD1-PB5{slash}SPI1_MOSI{slash}SPI3_MOSI{slash}I2S3_SD{slash}I2C1_SMBA{slash}TIM3_CH2-Pad41)") (class "Default")
      (node (ref "DD1") (pin "41") (pinfunction "PB5/SPI1_MOSI/SPI3_MOSI/I2S3_SD/I2C1_SMBA/TIM3_CH2_41") (pintype "passive"))
    )
    (net (code "74") (name "unconnected-(DD1-PB9{slash}SPI2_NSS{slash}I2S2_WS{slash}I2C1_SDA{slash}TIM4_CH4{slash}TIM11_CH1{slash}SDIO_D5-Pad46)") (class "Default")
      (node (ref "DD1") (pin "46") (pinfunction "PB9/SPI2_NSS/I2S2_WS/I2C1_SDA/TIM4_CH4/TIM11_CH1/SDIO_D5_46") (pintype "passive"))
    )
    (net (code "75") (name "unconnected-(DD1-PB10{slash}SPI2_SCK{slash}I2S2_CK{slash}I2C2_SCL{slash}TIM2_CH3-Pad21)") (class "Default")
      (node (ref "DD1") (pin "21") (pinfunction "PB10/SPI2_SCK/I2S2_CK/I2C2_SCL/TIM2_CH3_21") (pintype "passive"))
    )
    (net (code "76") (name "unconnected-(DD1-PC13-Pad2)") (class "Default")
      (node (ref "DD1") (pin "2") (pinfunction "PC13_2") (pintype "passive"))
    )
    (net (code "77") (name "unconnected-(DD1-PC14-OSC32_IN-Pad3)") (class "Default")
      (node (ref "DD1") (pin "3") (pinfunction "PC14-OSC32_IN_3") (pintype "passive"))
    )
    (net (code "78") (name "unconnected-(DD1-PC15-OSC32_OUT-Pad4)") (class "Default")
      (node (ref "DD1") (pin "4") (pinfunction "PC15-OSC32_OUT_4") (pintype "passive"))
    )
  )
)
